# legs_new.net
KiCad netlist of a schematic drawn in EAGLE
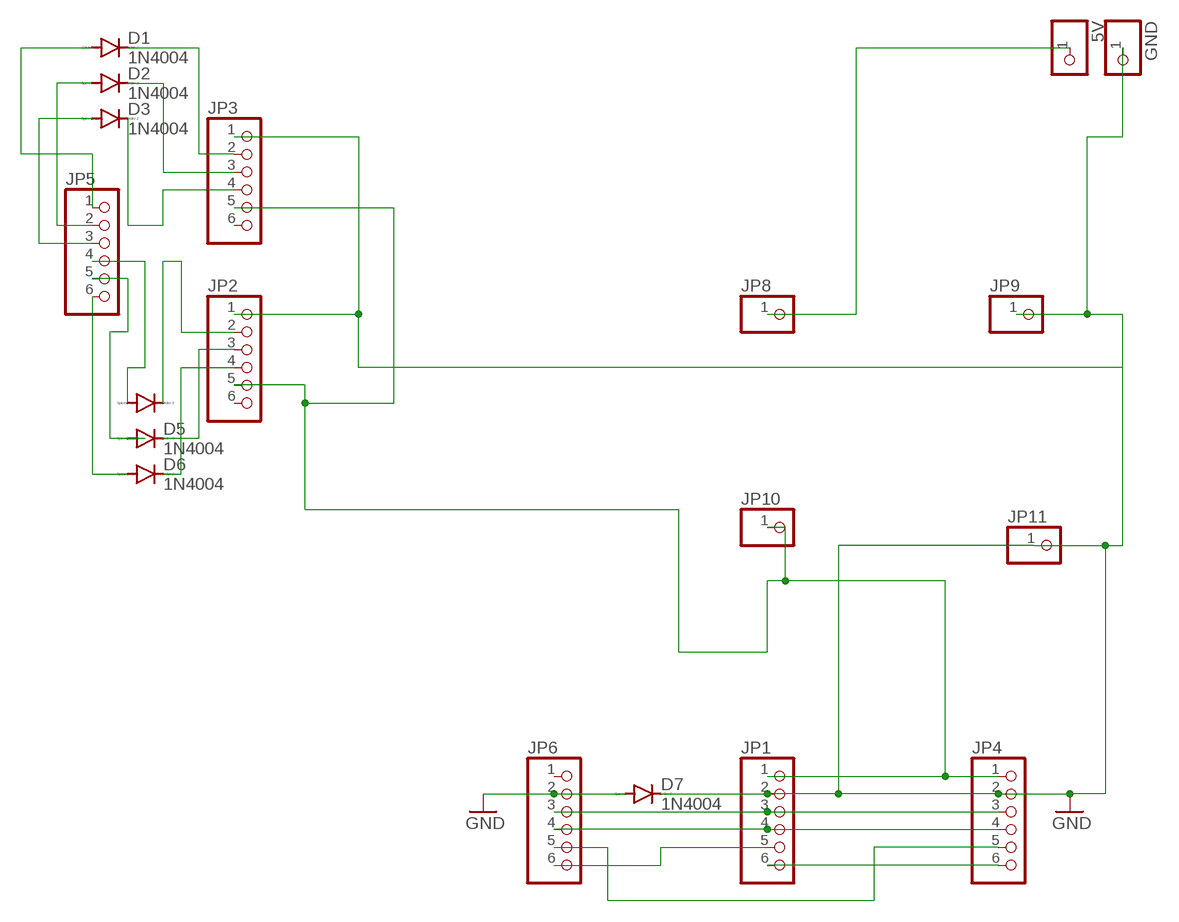
[diagram p0: schematic, sheet 1]

(export (version "E")
  (design (tool "Eeschema 10.0.6"))
  (components
    (comp (ref "5V")
      (value "PINHD-1X1")
      (footprint "eagle-import:1X01")
      (libsource (lib "eagle-import") (part "PINHD-1X1"))
    )
    (comp (ref "D1")
      (value "1N4004")
      (footprint "eagle-import:DO41-10")
      (libsource (lib "eagle-import") (part "1N4004"))
    )
    (comp (ref "D2")
      (value "1N4004")
      (footprint "eagle-import:DO41-10")
      (libsource (lib "eagle-import") (part "1N4004"))
    )
    (comp (ref "D3")
      (value "1N4004")
      (footprint "eagle-import:DO41-10")
      (libsource (lib "eagle-import") (part "1N4004"))
    )
    (comp (ref "D4")
      (value "1N4004")
      (footprint "eagle-import:DO41-10")
      (libsource (lib "eagle-import") (part "1N4004"))
    )
    (comp (ref "D5")
      (value "1N4004")
      (footprint "eagle-import:DO41-10")
      (libsource (lib "eagle-import") (part "1N4004"))
    )
    (comp (ref "D6")
      (value "1N4004")
      (footprint "eagle-import:DO41-10")
      (libsource (lib "eagle-import") (part "1N4004"))
    )
    (comp (ref "D7")
      (value "1N4004")
      (footprint "eagle-import:DO41-10")
      (libsource (lib "eagle-import") (part "1N4004"))
    )
    (comp (ref "GND")
      (value "PINHD-1X1")
      (footprint "eagle-import:1X01")
      (libsource (lib "eagle-import") (part "PINHD-1X1"))
    )
    (comp (ref "JP1")
      (value "PINHD-1X6")
      (footprint "eagle-import:1X06")
      (libsource (lib "eagle-import") (part "PINHD-1X6"))
    )
    (comp (ref "JP2")
      (value "PINHD-1X6")
      (footprint "eagle-import:1X06")
      (libsource (lib "eagle-import") (part "PINHD-1X6"))
    )
    (comp (ref "JP3")
      (value "PINHD-1X6")
      (footprint "eagle-import:1X06")
      (libsource (lib "eagle-import") (part "PINHD-1X6"))
    )
    (comp (ref "JP4")
      (value "PINHD-1X6")
      (footprint "eagle-import:1X06")
      (libsource (lib "eagle-import") (part "PINHD-1X6"))
    )
    (comp (ref "JP5")
      (value "PINHD-1X6")
      (footprint "eagle-import:1X06")
      (libsource (lib "eagle-import") (part "PINHD-1X6"))
    )
    (comp (ref "JP6")
      (value "PINHD-1X6")
      (footprint "eagle-import:1X06")
      (libsource (lib "eagle-import") (part "PINHD-1X6"))
    )
    (comp (ref "JP8")
      (value "PINHD-1X1")
      (footprint "eagle-import:1X01")
      (libsource (lib "eagle-import") (part "PINHD-1X1"))
    )
    (comp (ref "JP9")
      (value "PINHD-1X1")
      (footprint "eagle-import:1X01")
      (libsource (lib "eagle-import") (part "PINHD-1X1"))
    )
    (comp (ref "JP10")
      (value "PINHD-1X1")
      (footprint "eagle-import:1X01")
      (libsource (lib "eagle-import") (part "PINHD-1X1"))
    )
    (comp (ref "JP11")
      (value "PINHD-1X1")
      (footprint "eagle-import:1X01")
      (libsource (lib "eagle-import") (part "PINHD-1X1"))
    )
  )
  (nets
    (net (code "1") (name "GND") (class "Default")
      (node (ref "D7") (pin "A") (pinfunction "A_A") (pintype "passive"))
      (node (ref "D7") (pin "C") (pinfunction "C_C") (pintype "passive"))
      (node (ref "GND") (pin "1") (pinfunction "1_1") (pintype "passive"))
      (node (ref "JP1") (pin "2") (pinfunction "2_2") (pintype "passive"))
      (node (ref "JP11") (pin "1") (pinfunction "1_1") (pintype "passive"))
      (node (ref "JP2") (pin "1") (pinfunction "1_1") (pintype "passive"))
      (node (ref "JP3") (pin "1") (pinfunction "1_1") (pintype "passive"))
      (node (ref "JP4") (pin "2") (pinfunction "2_2") (pintype "passive"))
      (node (ref "JP6") (pin "2") (pinfunction "2_2") (pintype "passive"))
      (node (ref "JP9") (pin "1") (pinfunction "1_1") (pintype "passive"))
    )
    (net (code "2") (name "Net-(5V-Pad1)") (class "Default")
      (node (ref "5V") (pin "1") (pinfunction "1_1") (pintype "passive"))
      (node (ref "JP8") (pin "1") (pinfunction "1_1") (pintype "passive"))
    )
    (net (code "3") (name "Net-(D1-PadA)") (class "Default")
      (node (ref "D1") (pin "A") (pinfunction "A_A") (pintype "passive"))
      (node (ref "JP5") (pin "1") (pinfunction "1_1") (pintype "passive"))
    )
    (net (code "4") (name "Net-(D1-PadC)") (class "Default")
      (node (ref "D1") (pin "C") (pinfunction "C_C") (pintype "passive"))
      (node (ref "JP3") (pin "2") (pinfunction "2_2") (pintype "passive"))
    )
    (net (code "5") (name "Net-(D2-PadA)") (class "Default")
      (node (ref "D2") (pin "A") (pinfunction "A_A") (pintype "passive"))
      (node (ref "JP5") (pin "2") (pinfunction "2_2") (pintype "passive"))
    )
    (net (code "6") (name "Net-(D2-PadC)") (class "Default")
      (node (ref "D2") (pin "C") (pinfunction "C_C") (pintype "passive"))
      (node (ref "JP3") (pin "3") (pinfunction "3_3") (pintype "passive"))
    )
    (net (code "7") (name "Net-(D3-PadA)") (class "Default")
      (node (ref "D3") (pin "A") (pinfunction "A_A") (pintype "passive"))
      (node (ref "JP5") (pin "3") (pinfunction "3_3") (pintype "passive"))
    )
    (net (code "8") (name "Net-(D3-PadC)") (class "Default")
      (node (ref "D3") (pin "C") (pinfunction "C_C") (pintype "passive"))
      (node (ref "JP3") (pin "4") (pinfunction "4_4") (pintype "passive"))
    )
    (net (code "9") (name "Net-(D4-PadA)") (class "Default")
      (node (ref "D4") (pin "A") (pinfunction "A_A") (pintype "passive"))
      (node (ref "JP5") (pin "4") (pinfunction "4_4") (pintype "passive"))
    )
    (net (code "10") (name "Net-(D4-PadC)") (class "Default")
      (node (ref "D4") (pin "C") (pinfunction "C_C") (pintype "passive"))
      (node (ref "JP2") (pin "2") (pinfunction "2_2") (pintype "passive"))
    )
    (net (code "11") (name "Net-(D5-PadA)") (class "Default")
      (node (ref "D5") (pin "A") (pinfunction "A_A") (pintype "passive"))
      (node (ref "JP5") (pin "5") (pinfunction "5_5") (pintype "passive"))
    )
    (net (code "12") (name "Net-(D5-PadC)") (class "Default")
      (node (ref "D5") (pin "C") (pinfunction "C_C") (pintype "passive"))
      (node (ref "JP2") (pin "3") (pinfunction "3_3") (pintype "passive"))
    )
    (net (code "13") (name "Net-(D6-PadA)") (class "Default")
      (node (ref "D6") (pin "A") (pinfunction "A_A") (pintype "passive"))
      (node (ref "JP5") (pin "6") (pinfunction "6_6") (pintype "passive"))
    )
    (net (code "14") (name "Net-(D6-PadC)") (class "Default")
      (node (ref "D6") (pin "C") (pinfunction "C_C") (pintype "passive"))
      (node (ref "JP2") (pin "4") (pinfunction "4_4") (pintype "passive"))
    )
    (net (code "15") (name "Net-(JP1-Pad1)") (class "Default")
      (node (ref "JP1") (pin "1") (pinfunction "1_1") (pintype "passive"))
      (node (ref "JP10") (pin "1") (pinfunction "1_1") (pintype "passive"))
      (node (ref "JP2") (pin "5") (pinfunction "5_5") (pintype "passive"))
      (node (ref "JP3") (pin "5") (pinfunction "5_5") (pintype "passive"))
      (node (ref "JP4") (pin "1") (pinfunction "1_1") (pintype "passive"))
    )
    (net (code "16") (name "Net-(JP1-Pad3)") (class "Default")
      (node (ref "JP1") (pin "3") (pinfunction "3_3") (pintype "passive"))
      (node (ref "JP4") (pin "3") (pinfunction "3_3") (pintype "passive"))
      (node (ref "JP6") (pin "3") (pinfunction "3_3") (pintype "passive"))
    )
    (net (code "17") (name "Net-(JP1-Pad4)") (class "Default")
      (node (ref "JP1") (pin "4") (pinfunction "4_4") (pintype "passive"))
      (node (ref "JP4") (pin "4") (pinfunction "4_4") (pintype "passive"))
      (node (ref "JP6") (pin "4") (pinfunction "4_4") (pintype "passive"))
    )
    (net (code "18") (name "Net-(JP1-Pad5)") (class "Default")
      (node (ref "JP1") (pin "5") (pinfunction "5_5") (pintype "passive"))
      (node (ref "JP6") (pin "6") (pinfunction "6_6") (pintype "passive"))
    )
    (net (code "19") (name "Net-(JP1-Pad6)") (class "Default")
      (node (ref "JP1") (pin "6") (pinfunction "6_6") (pintype "passive"))
      (node (ref "JP4") (pin "6") (pinfunction "6_6") (pintype "passive"))
    )
    (net (code "20") (name "Net-(JP4-Pad5)") (class "Default")
      (node (ref "JP4") (pin "5") (pinfunction "5_5") (pintype "passive"))
      (node (ref "JP6") (pin "5") (pinfunction "5_5") (pintype "passive"))
    )
    (net (code "21") (name "unconnected-(JP2-Pad6)") (class "Default")
      (node (ref "JP2") (pin "6") (pinfunction "6_6") (pintype "passive"))
    )
    (net (code "22") (name "unconnected-(JP3-Pad6)") (class "Default")
      (node (ref "JP3") (pin "6") (pinfunction "6_6") (pintype "passive"))
    )
    (net (code "23") (name "unconnected-(JP6-Pad1)") (class "Default")
      (node (ref "JP6") (pin "1") (pinfunction "1_1") (pintype "passive"))
    )
  )
)
